# PCA4595A_4-ch_I2C_Switch.net
KiCad netlist of a schematic drawn in Altium Designer
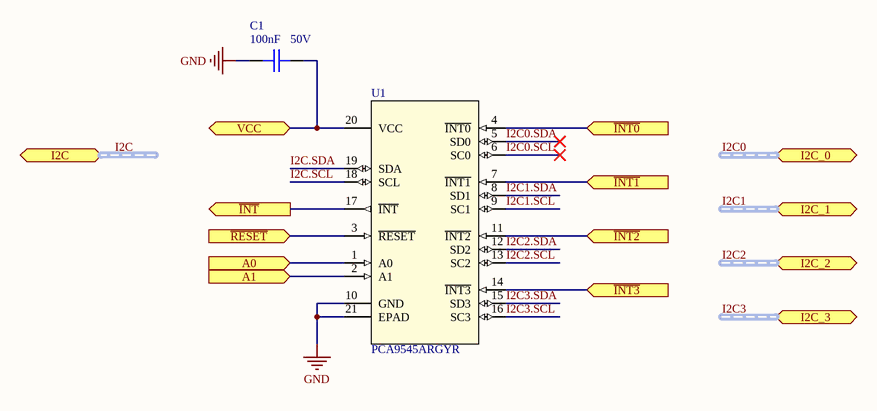
[diagram p0: PCA4595A_4-ch_I2C_Switch.SchDoc]

(export (version "E")
  (design (tool "Eeschema 10.0.6"))
  (components
    (comp (ref "C1")
      (value "CGA2B3X7R1H104K050BB")
      (footprint "C0402")
      (description "0.1µF ±10% 50V Ceramic Capacitor X7R 0402 (1005 Metric)")
      (fields
        (field (name "MANUFACTURER") "TDK")
        (field (name "TOLERANCE") "10%")
        (field (name "CAPACITANCE") "100nF")
        (field (name "VOLTAGE") "50V")
      )
      (libsource (lib "capacitors_smd") (part "CAP CER 0.1UF 50V X7R 0402"))
    )
    (comp (ref "U1")
      (value "PCA9545ARGYR")
      (footprint "RGY20_3P05X2P05")
      (description "4-Channel I2C And SMBus Multiplexer With Interrupt Logic And Reset Functions")
      (fields (field (name "MANUFACTURER") "Texas Instruments"))
      (libsource (lib "ic_i2c_interface") (part "IC PCA9545A I2C SW 4CH W/RESET 20VQFN"))
    )
  )
  (nets
    (net (code "6") (name "/A0") (class "Default")
      (node (ref "U1") (pin "1") (pinfunction "A0_1") (pintype "input"))
    )
    (net (code "7") (name "/A1") (class "Default")
      (node (ref "U1") (pin "2") (pinfunction "A1_2") (pintype "input"))
    )
    (net (code "8") (name "/I2C.SCL") (class "Default")
      (node (ref "U1") (pin "18") (pinfunction "SCL_18") (pintype "bidirectional"))
    )
    (net (code "9") (name "/I2C.SDA") (class "Default")
      (node (ref "U1") (pin "19") (pinfunction "SDA_19") (pintype "bidirectional"))
    )
    (net (code "10") (name "/I2C0.SCL") (class "Default")
      (node (ref "U1") (pin "6") (pinfunction "SC0_6") (pintype "bidirectional+no_connect"))
    )
    (net (code "11") (name "/I2C0.SDA") (class "Default")
      (node (ref "U1") (pin "5") (pinfunction "SD0_5") (pintype "bidirectional+no_connect"))
    )
    (net (code "12") (name "/I2C1.SCL") (class "Default")
      (node (ref "U1") (pin "9") (pinfunction "SC1_9") (pintype "bidirectional"))
    )
    (net (code "13") (name "/I2C1.SDA") (class "Default")
      (node (ref "U1") (pin "8") (pinfunction "SD1_8") (pintype "bidirectional"))
    )
    (net (code "14") (name "/I2C2.SCL") (class "Default")
      (node (ref "U1") (pin "13") (pinfunction "SC2_13") (pintype "bidirectional"))
    )
    (net (code "15") (name "/I2C2.SDA") (class "Default")
      (node (ref "U1") (pin "12") (pinfunction "SD2_12") (pintype "bidirectional"))
    )
    (net (code "16") (name "/I2C3.SCL") (class "Default")
      (node (ref "U1") (pin "16") (pinfunction "SC3_16") (pintype "bidirectional"))
    )
    (net (code "17") (name "/I2C3.SDA") (class "Default")
      (node (ref "U1") (pin "15") (pinfunction "SD3_15") (pintype "bidirectional"))
    )
    (net (code "18") (name "/INT") (class "Default")
      (node (ref "U1") (pin "17") (pinfunction "INT_17") (pintype "output"))
    )
    (net (code "19") (name "/INT0") (class "Default")
      (node (ref "U1") (pin "4") (pinfunction "INT0_4") (pintype "input"))
    )
    (net (code "20") (name "/INT1") (class "Default")
      (node (ref "U1") (pin "7") (pinfunction "INT1_7") (pintype "input"))
    )
    (net (code "21") (name "/INT2") (class "Default")
      (node (ref "U1") (pin "11") (pinfunction "INT2_11") (pintype "input"))
    )
    (net (code "22") (name "/INT3") (class "Default")
      (node (ref "U1") (pin "14") (pinfunction "INT3_14") (pintype "input"))
    )
    (net (code "23") (name "/RESET") (class "Default")
      (node (ref "U1") (pin "3") (pinfunction "RESET_3") (pintype "input"))
    )
    (net (code "24") (name "/VCC") (class "Default")
      (node (ref "C1") (pin "1") (pinfunction "1_1") (pintype "passive"))
      (node (ref "U1") (pin "20") (pinfunction "VCC_20") (pintype "power_in"))
    )
    (net (code "30") (name "GND") (class "Default")
      (node (ref "C1") (pin "2") (pinfunction "2_2") (pintype "passive"))
      (node (ref "U1") (pin "10") (pinfunction "GND_10") (pintype "power_in"))
      (node (ref "U1") (pin "21") (pinfunction "EPAD_21") (pintype "power_in"))
    )
  )
)
